# PlacaSubsat_lite.net
KiCad netlist of a schematic drawn in EAGLE
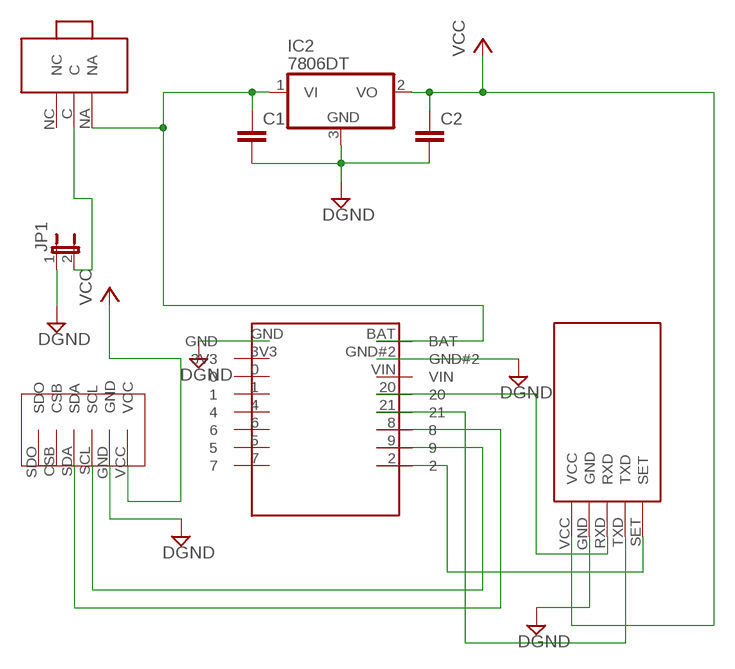
[diagram p0: schematic, sheet 1]

(export (version "E")
  (design (tool "Eeschema 10.0.6"))
  (components
    (comp (ref "C1")
      (value "C-EUC1210")
      (footprint "eagle-import:C1210")
      (libsource (lib "eagle-import") (part "C-EUC1210"))
    )
    (comp (ref "C2")
      (value "C-EUC1210")
      (footprint "eagle-import:C1210")
      (libsource (lib "eagle-import") (part "C-EUC1210"))
    )
    (comp (ref "IC2")
      (value "7806DT")
      (footprint "eagle-import:TO252")
      (libsource (lib "eagle-import") (part "78DT06"))
    )
    (comp (ref "JP1")
      (value "JP1E")
      (footprint "eagle-import:JP1")
      (libsource (lib "eagle-import") (part "JP1E"))
    )
    (comp (ref "U$1")
      (value "BMP280")
      (footprint "eagle-import:BMP280")
      (libsource (lib "eagle-import") (part "BMP280"))
    )
    (comp (ref "U$2")
      (value "MODULO_RADIO")
      (footprint "eagle-import:MÓDULO_RADIO")
      (libsource (lib "eagle-import") (part "MODULO_RADIO"))
    )
    (comp (ref "U$3")
      (value "ESP32")
      (footprint "eagle-import:ESP32")
      (libsource (lib "eagle-import") (part "ESP32"))
    )
    (comp (ref "U$4")
      (value "SWITCH")
      (footprint "eagle-import:SWITCH")
      (libsource (lib "eagle-import") (part "SWITCH"))
    )
  )
  (nets
    (net (code "1") (name "DGND") (class "Default")
      (node (ref "C1") (pin "2") (pinfunction "2_2") (pintype "passive"))
      (node (ref "C2") (pin "2") (pinfunction "2_2") (pintype "passive"))
      (node (ref "IC2") (pin "3") (pinfunction "GND_3") (pintype "passive"))
      (node (ref "JP1") (pin "1") (pinfunction "1_1") (pintype "passive"))
      (node (ref "U$1") (pin "GND") (pinfunction "GND_GND") (pintype "bidirectional"))
      (node (ref "U$2") (pin "GND") (pinfunction "GND_GND") (pintype "bidirectional"))
      (node (ref "U$3") (pin "GND") (pinfunction "GND_GND") (pintype "bidirectional"))
      (node (ref "U$3") (pin "GND#2") (pinfunction "GND#2_GND#2") (pintype "bidirectional"))
    )
    (net (code "2") (name "Net-(IC2-VI)") (class "Default")
      (node (ref "C1") (pin "1") (pinfunction "1_1") (pintype "passive"))
      (node (ref "IC2") (pin "1") (pinfunction "VI_1") (pintype "input"))
      (node (ref "U$3") (pin "BAT") (pinfunction "BAT_BAT") (pintype "bidirectional"))
      (node (ref "U$4") (pin "NA") (pinfunction "NA_NA") (pintype "bidirectional"))
    )
    (net (code "3") (name "Net-(JP1-Pad2)") (class "Default")
      (node (ref "JP1") (pin "2") (pinfunction "2_2") (pintype "passive"))
      (node (ref "U$4") (pin "C") (pinfunction "C_C") (pintype "bidirectional"))
    )
    (net (code "4") (name "Net-(U$1-PadCSB)") (class "Default")
      (node (ref "U$1") (pin "CSB") (pinfunction "CSB_CSB") (pintype "bidirectional"))
      (node (ref "U$1") (pin "SDO") (pinfunction "SDO_SDO") (pintype "bidirectional"))
    )
    (net (code "5") (name "Net-(U$1-PadSCL)") (class "Default")
      (node (ref "U$1") (pin "SCL") (pinfunction "SCL_SCL") (pintype "bidirectional"))
      (node (ref "U$3") (pin "9") (pinfunction "9_9") (pintype "bidirectional"))
    )
    (net (code "6") (name "Net-(U$1-PadSDA)") (class "Default")
      (node (ref "U$1") (pin "SDA") (pinfunction "SDA_SDA") (pintype "bidirectional"))
      (node (ref "U$3") (pin "8") (pinfunction "8_8") (pintype "bidirectional"))
    )
    (net (code "7") (name "Net-(U$2-PadRXD)") (class "Default")
      (node (ref "U$2") (pin "RXD") (pinfunction "RXD_RXD") (pintype "bidirectional"))
      (node (ref "U$3") (pin "20") (pinfunction "20_20") (pintype "bidirectional"))
    )
    (net (code "8") (name "Net-(U$2-PadSET)") (class "Default")
      (node (ref "U$2") (pin "SET") (pinfunction "SET_SET") (pintype "bidirectional"))
      (node (ref "U$3") (pin "2") (pinfunction "2_2") (pintype "bidirectional"))
    )
    (net (code "9") (name "Net-(U$2-PadTXD)") (class "Default")
      (node (ref "U$2") (pin "TXD") (pinfunction "TXD_TXD") (pintype "bidirectional"))
      (node (ref "U$3") (pin "21") (pinfunction "21_21") (pintype "bidirectional"))
    )
    (net (code "10") (name "VCC") (class "Default")
      (node (ref "C2") (pin "1") (pinfunction "1_1") (pintype "passive"))
      (node (ref "IC2") (pin "2") (pinfunction "VO_2") (pintype "passive"))
      (node (ref "U$1") (pin "VCC") (pinfunction "VCC_VCC") (pintype "bidirectional"))
      (node (ref "U$2") (pin "VCC") (pinfunction "VCC_VCC") (pintype "bidirectional"))
    )
    (net (code "11") (name "unconnected-(U$3-Pad0)") (class "Default")
      (node (ref "U$3") (pin "0") (pinfunction "0_0") (pintype "bidirectional"))
    )
    (net (code "12") (name "unconnected-(U$3-Pad1)") (class "Default")
      (node (ref "U$3") (pin "1") (pinfunction "1_1") (pintype "bidirectional"))
    )
    (net (code "13") (name "unconnected-(U$3-Pad3V3)") (class "Default")
      (node (ref "U$3") (pin "3V3") (pinfunction "3V3_3V3") (pintype "bidirectional"))
    )
    (net (code "14") (name "unconnected-(U$3-Pad4)") (class "Default")
      (node (ref "U$3") (pin "4") (pinfunction "4_4") (pintype "bidirectional"))
    )
    (net (code "15") (name "unconnected-(U$3-Pad5)") (class "Default")
      (node (ref "U$3") (pin "5") (pinfunction "5_5") (pintype "bidirectional"))
    )
    (net (code "16") (name "unconnected-(U$3-Pad6)") (class "Default")
      (node (ref "U$3") (pin "6") (pinfunction "6_6") (pintype "bidirectional"))
    )
    (net (code "17") (name "unconnected-(U$3-Pad7)") (class "Default")
      (node (ref "U$3") (pin "7") (pinfunction "7_7") (pintype "bidirectional"))
    )
    (net (code "18") (name "unconnected-(U$3-PadVIN)") (class "Default")
      (node (ref "U$3") (pin "VIN") (pinfunction "VIN_VIN") (pintype "bidirectional"))
    )
    (net (code "19") (name "unconnected-(U$4-PadNC)") (class "Default")
      (node (ref "U$4") (pin "NC") (pinfunction "NC_NC") (pintype "bidirectional"))
    )
  )
)
